# boxer_stm32.net
KiCad netlist of a schematic drawn in Altium Designer
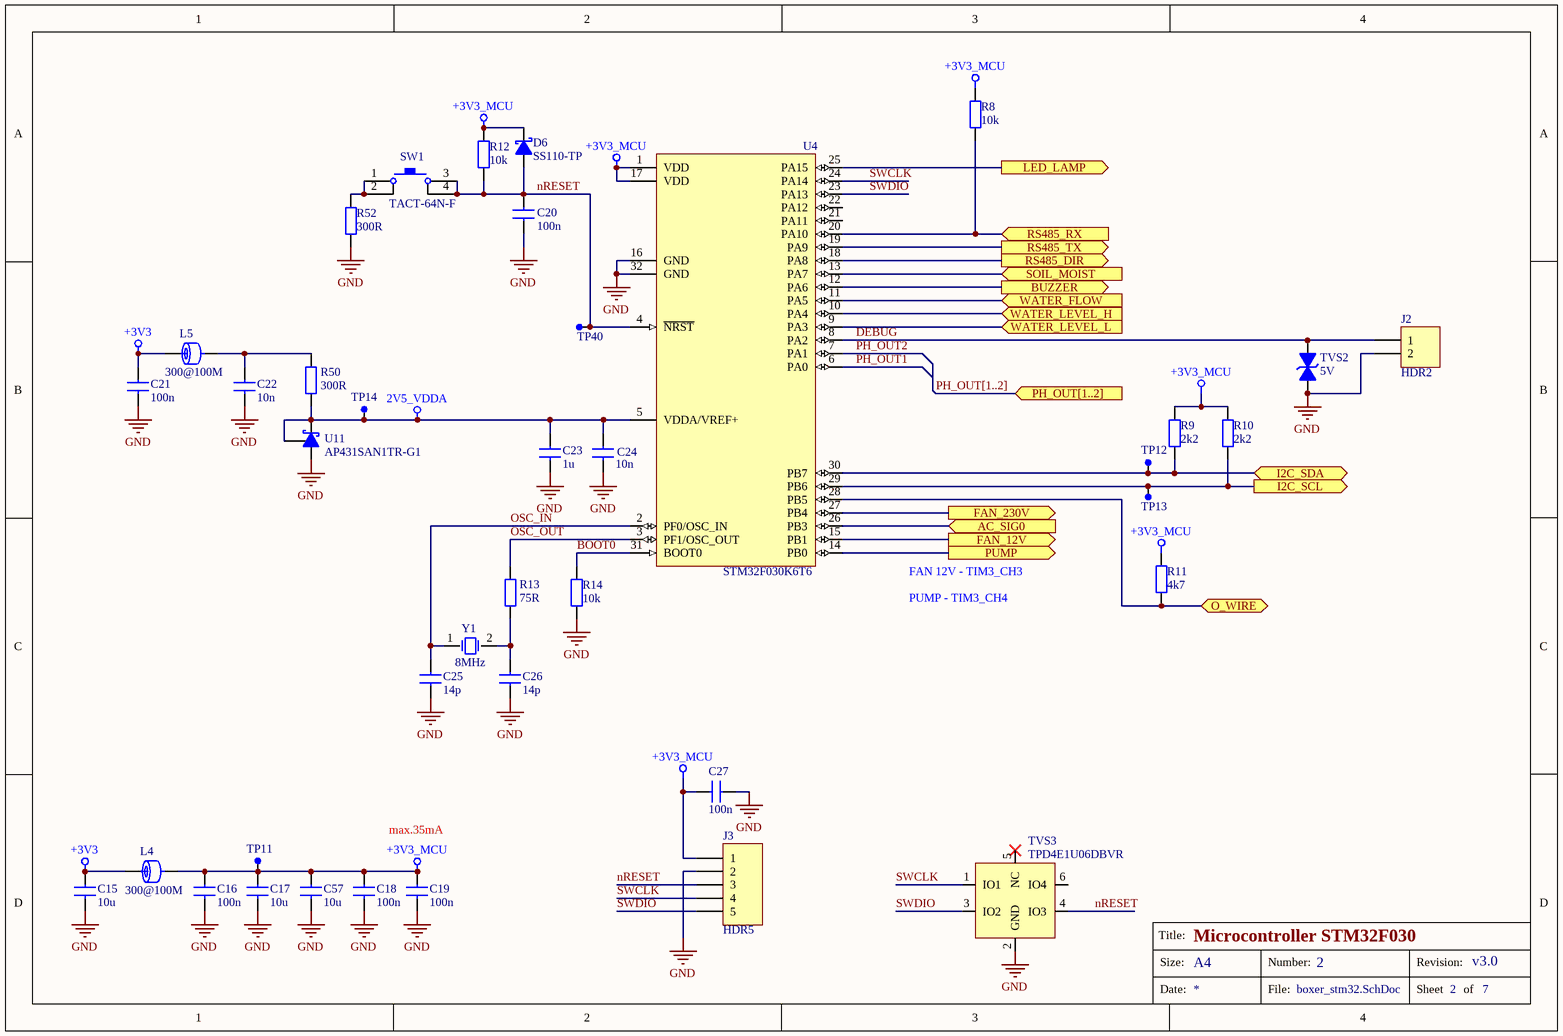
[diagram p0: boxer_stm32.SchDoc]

(export (version "E")
  (design (tool "Eeschema 10.0.6"))
  (components
    (comp (ref "C15")
      (value "10u")
      (footprint "C_1206")
      (description "Capacitor")
      (libsource (lib "boxer_pas") (part "Capacitor"))
    )
    (comp (ref "C16")
      (value "100n")
      (footprint "C_0805")
      (description "Capacitor")
      (libsource (lib "boxer_pas") (part "Capacitor"))
    )
    (comp (ref "C17")
      (value "10u")
      (footprint "C_1206")
      (description "Capacitor")
      (fields (field (name "Comment") "TME: CL31A226MOCLNNC"))
      (libsource (lib "boxer_pas") (part "Capacitor"))
    )
    (comp (ref "C18")
      (value "100n")
      (footprint "C_0805")
      (description "Capacitor")
      (libsource (lib "boxer_pas") (part "Capacitor"))
    )
    (comp (ref "C19")
      (value "100n")
      (footprint "C_0805")
      (description "Capacitor")
      (libsource (lib "boxer_pas") (part "Capacitor"))
    )
    (comp (ref "C20")
      (value "100n")
      (footprint "C_0805")
      (description "Capacitor")
      (libsource (lib "boxer_pas") (part "Capacitor"))
    )
    (comp (ref "C21")
      (value "100n")
      (footprint "C_0805")
      (description "Capacitor")
      (libsource (lib "boxer_pas") (part "Capacitor"))
    )
    (comp (ref "C22")
      (value "10n")
      (footprint "C_0805")
      (description "Capacitor")
      (libsource (lib "boxer_pas") (part "Capacitor"))
    )
    (comp (ref "C23")
      (value "1u")
      (footprint "C_0805")
      (description "Capacitor")
      (fields (field (name "Comment") "C0805C105K4RACAUTO"))
      (libsource (lib "boxer_pas") (part "Capacitor"))
    )
    (comp (ref "C24")
      (value "10n")
      (footprint "C_0805")
      (description "Capacitor")
      (libsource (lib "boxer_pas") (part "Capacitor"))
    )
    (comp (ref "C25")
      (value "14p")
      (footprint "C_0805")
      (description "Capacitor")
      (fields (field (name "Comment") "490-14443-1-ND"))
      (libsource (lib "boxer_pas") (part "Capacitor"))
    )
    (comp (ref "C26")
      (value "14p")
      (footprint "C_0805")
      (description "Capacitor")
      (fields (field (name "Comment") "490-14443-1-ND"))
      (libsource (lib "boxer_pas") (part "Capacitor"))
    )
    (comp (ref "C27")
      (value "100n")
      (footprint "C_0805")
      (description "Capacitor")
      (libsource (lib "boxer_pas") (part "Capacitor"))
    )
    (comp (ref "C57")
      (value "10u")
      (footprint "C_1206")
      (description "Capacitor")
      (fields (field (name "Comment") "TME: CL31A226MOCLNNC"))
      (libsource (lib "boxer_pas") (part "Capacitor"))
    )
    (comp (ref "D6")
      (value "SS110-TP")
      (footprint "D_1206")
      (description "Schottky Diode")
      (libsource (lib "boxer_pas") (part "Diode Schottky"))
    )
    (comp (ref "J2")
      (value "HDR2")
      (footprint "header 2.54mm 2pin")
      (description "Header, 2-Pin")
      (fields (field (name "Comment") "Header 2.54mm"))
      (libsource (lib "boxer_mechanical") (part "Header 2"))
    )
    (comp (ref "J3")
      (value "HDR5")
      (footprint "boxer_mechanical:header 2.54mm 5pin")
      (description "Header, 5-Pin")
      (fields (field (name "Comment") "Header 2.54mm"))
      (libsource (lib "boxer_mechanical") (part "Header 5"))
    )
    (comp (ref "L4")
      (value "300@100M")
      (footprint "L_0805")
      (description "Ferrite Bead")
      (fields (field (name "Comment") "742792031"))
      (libsource (lib "boxer_pas") (part "FB"))
    )
    (comp (ref "L5")
      (value "300@100M")
      (footprint "L_0805")
      (description "Ferrite Bead")
      (fields (field (name "Comment") "742792031"))
      (libsource (lib "boxer_pas") (part "FB"))
    )
    (comp (ref "R8")
      (value "10k")
      (footprint "R_1206")
      (description "Resistor")
      (libsource (lib "boxer_pas") (part "Resistor"))
    )
    (comp (ref "R9")
      (value "2k2")
      (footprint "R_0805")
      (description "Resistor")
      (libsource (lib "boxer_pas") (part "Resistor"))
    )
    (comp (ref "R10")
      (value "2k2")
      (footprint "R_0805")
      (description "Resistor")
      (libsource (lib "boxer_pas") (part "Resistor"))
    )
    (comp (ref "R11")
      (value "4k7")
      (footprint "R_0805")
      (description "Resistor")
      (libsource (lib "") (part "Resistor_1"))
    )
    (comp (ref "R12")
      (value "10k")
      (footprint "R_1206")
      (description "Resistor")
      (libsource (lib "boxer_pas") (part "Resistor"))
    )
    (comp (ref "R13")
      (value "75R")
      (footprint "R_0805")
      (description "Resistor")
      (libsource (lib "boxer_pas") (part "Resistor"))
    )
    (comp (ref "R14")
      (value "10k")
      (footprint "R_1206")
      (description "Resistor")
      (libsource (lib "boxer_pas") (part "Resistor"))
    )
    (comp (ref "R50")
      (value "300R")
      (footprint "R_0805")
      (description "Resistor")
      (libsource (lib "boxer_pas") (part "Resistor"))
    )
    (comp (ref "R52")
      (value "300R")
      (footprint "R_0805")
      (description "Resistor")
      (libsource (lib "") (part "Resistor_1"))
    )
    (comp (ref "SW1")
      (value "TACT-64N-F")
      (footprint "SPST_NO_1301")
      (description "Switch 4 Pins")
      (libsource (lib "boxer_mechanical") (part "Switch-PB 4 Pins"))
    )
    (comp (ref "TP11")
      (value "TEST PAD")
      (footprint "PIN")
      (description "PAD 1.5mm")
      (libsource (lib "boxer_mechanical") (part "TEST_PAD"))
    )
    (comp (ref "TP12")
      (value "TEST PAD")
      (footprint "PIN")
      (libsource (lib "boxer_mechanical") (part "TEST_PAD"))
    )
    (comp (ref "TP13")
      (value "TEST PAD")
      (footprint "PIN")
      (libsource (lib "boxer_mechanical") (part "TEST_PAD"))
    )
    (comp (ref "TP14")
      (value "TEST PAD")
      (footprint "PIN")
      (description "PAD 1.5mm")
      (libsource (lib "boxer_mechanical") (part "TEST_PAD"))
    )
    (comp (ref "TP40")
      (value "TEST PAD")
      (footprint "PIN")
      (description "PAD 1.5mm")
      (libsource (lib "boxer_mechanical") (part "TEST_PAD"))
    )
    (comp (ref "TVS2")
      (value "5V")
      (footprint "D_SMA")
      (description "Transil")
      (fields (field (name "Comment") "SMAJ5.0ALFCT-ND"))
      (libsource (lib "boxer_pas") (part "Transil"))
    )
    (comp (ref "TVS3")
      (value "TPD4E1U06DBVR")
      (footprint "SOT23-6")
      (description "TVS Array")
      (libsource (lib "boxer_pas") (part "Transil Array_2"))
    )
    (comp (ref "U4")
      (value "STM32F030K6T6")
      (footprint "LQFP-32")
      (description "Microcontroler ARM; Flash:32kB; 48MHz; SRAM:4kB; LQFP32")
      (libsource (lib "boxer_ic") (part "STM32F030C8T6"))
    )
    (comp (ref "U11")
      (value "AP431SAN1TR-G1")
      (footprint "SOT-23")
      (libsource (lib "boxer_pas") (part "REF_VOLTAGE"))
    )
    (comp (ref "Y1")
      (value "8MHz")
      (footprint "CFPX_217")
      (description "Crystal Oscillator")
      (fields (field (name "Comment") "7A-8.000MAAE-T"))
      (libsource (lib "boxer_pas") (part "XTAL"))
    )
  )
  (nets
    (net (code "1") (name "+3V3") (class "Default")
      (node (ref "C15") (pin "2") (pinfunction "2_2") (pintype "passive"))
      (node (ref "C21") (pin "2") (pinfunction "2_2") (pintype "passive"))
      (node (ref "L4") (pin "1") (pinfunction "1_1") (pintype "passive"))
      (node (ref "L5") (pin "1") (pinfunction "1_1") (pintype "passive"))
    )
    (net (code "2") (name "+3V3_MCU") (class "Default")
      (node (ref "C16") (pin "2") (pinfunction "2_2") (pintype "passive"))
      (node (ref "C17") (pin "2") (pinfunction "2_2") (pintype "passive"))
      (node (ref "C18") (pin "2") (pinfunction "2_2") (pintype "passive"))
      (node (ref "C19") (pin "2") (pinfunction "2_2") (pintype "passive"))
      (node (ref "C27") (pin "1") (pinfunction "1_1") (pintype "passive"))
      (node (ref "C57") (pin "1") (pinfunction "1_1") (pintype "passive"))
      (node (ref "D6") (pin "2") (pinfunction "K_2") (pintype "passive"))
      (node (ref "J3") (pin "1") (pinfunction "1_1") (pintype "passive"))
      (node (ref "L4") (pin "2") (pinfunction "2_2") (pintype "passive"))
      (node (ref "R10") (pin "2") (pinfunction "2_2") (pintype "passive"))
      (node (ref "R11") (pin "1") (pinfunction "1_1") (pintype "passive"))
      (node (ref "R12") (pin "2") (pinfunction "2_2") (pintype "passive"))
      (node (ref "R8") (pin "2") (pinfunction "2_2") (pintype "passive"))
      (node (ref "R9") (pin "2") (pinfunction "2_2") (pintype "passive"))
      (node (ref "TP11") (pin "1") (pinfunction "1_1") (pintype "passive"))
      (node (ref "U4") (pin "1") (pinfunction "VDD_1") (pintype "power_in"))
      (node (ref "U4") (pin "17") (pinfunction "VDD_17") (pintype "power_in"))
    )
    (net (code "3") (name "/AC_SIG0") (class "Default")
      (node (ref "U4") (pin "26") (pinfunction "PB3_26") (pintype "bidirectional"))
    )
    (net (code "4") (name "/BOOT0") (class "Default")
      (node (ref "R14") (pin "2") (pinfunction "2_2") (pintype "passive"))
      (node (ref "U4") (pin "31") (pinfunction "BOOT0_31") (pintype "input"))
    )
    (net (code "5") (name "/BUZZER") (class "Default")
      (node (ref "U4") (pin "12") (pinfunction "PA6_12") (pintype "bidirectional"))
    )
    (net (code "6") (name "/DEBUG") (class "Default")
      (node (ref "J2") (pin "1") (pinfunction "1_1") (pintype "passive"))
      (node (ref "TVS2") (pin "2") (pinfunction "K_2") (pintype "passive"))
      (node (ref "U4") (pin "8") (pinfunction "PA2_8") (pintype "bidirectional"))
    )
    (net (code "7") (name "/FAN_12V") (class "Default")
      (node (ref "U4") (pin "15") (pinfunction "PB1_15") (pintype "bidirectional"))
    )
    (net (code "8") (name "/FAN_230V") (class "Default")
      (node (ref "U4") (pin "27") (pinfunction "PB4_27") (pintype "bidirectional"))
    )
    (net (code "9") (name "/I2C_SCL") (class "Default")
      (node (ref "R10") (pin "1") (pinfunction "1_1") (pintype "passive"))
      (node (ref "TP13") (pin "1") (pinfunction "1_1") (pintype "passive"))
      (node (ref "U4") (pin "29") (pinfunction "PB6_29") (pintype "bidirectional"))
    )
    (net (code "10") (name "/I2C_SDA") (class "Default")
      (node (ref "R9") (pin "1") (pinfunction "1_1") (pintype "passive"))
      (node (ref "TP12") (pin "1") (pinfunction "1_1") (pintype "passive"))
      (node (ref "U4") (pin "30") (pinfunction "PB7_30") (pintype "bidirectional"))
    )
    (net (code "11") (name "/LED_LAMP") (class "Default")
      (node (ref "U4") (pin "25") (pinfunction "PA15_25") (pintype "bidirectional"))
    )
    (net (code "12") (name "/OSC_IN") (class "Default")
      (node (ref "C25") (pin "2") (pinfunction "2_2") (pintype "passive"))
      (node (ref "U4") (pin "2") (pinfunction "PF0/OSC_IN_2") (pintype "bidirectional"))
      (node (ref "Y1") (pin "1") (pinfunction "OSC1_1") (pintype "passive"))
    )
    (net (code "13") (name "/OSC_OUT") (class "Default")
      (node (ref "R13") (pin "2") (pinfunction "2_2") (pintype "passive"))
      (node (ref "U4") (pin "3") (pinfunction "PF1/OSC_OUT_3") (pintype "bidirectional"))
    )
    (net (code "14") (name "/O_WIRE") (class "Default")
      (node (ref "R11") (pin "2") (pinfunction "2_2") (pintype "passive"))
      (node (ref "U4") (pin "28") (pinfunction "PB5_28") (pintype "bidirectional"))
    )
    (net (code "15") (name "/PH_OUT1") (class "Default")
      (node (ref "U4") (pin "6") (pinfunction "PA0_6") (pintype "bidirectional"))
    )
    (net (code "16") (name "/PH_OUT2") (class "Default")
      (node (ref "U4") (pin "7") (pinfunction "PA1_7") (pintype "bidirectional"))
    )
    (net (code "18") (name "/PUMP") (class "Default")
      (node (ref "U4") (pin "14") (pinfunction "PB0_14") (pintype "bidirectional"))
    )
    (net (code "19") (name "/RS485_DIR") (class "Default")
      (node (ref "U4") (pin "18") (pinfunction "PA8_18") (pintype "bidirectional"))
    )
    (net (code "20") (name "/RS485_RX") (class "Default")
      (node (ref "R8") (pin "1") (pinfunction "1_1") (pintype "passive"))
      (node (ref "U4") (pin "20") (pinfunction "PA10_20") (pintype "bidirectional"))
    )
    (net (code "21") (name "/RS485_TX") (class "Default")
      (node (ref "U4") (pin "19") (pinfunction "PA9_19") (pintype "bidirectional"))
    )
    (net (code "22") (name "/SOIL_MOIST") (class "Default")
      (node (ref "U4") (pin "13") (pinfunction "PA7_13") (pintype "bidirectional"))
    )
    (net (code "23") (name "/SWCLK") (class "Default")
      (node (ref "J3") (pin "4") (pinfunction "4_4") (pintype "passive"))
      (node (ref "TVS3") (pin "1") (pinfunction "IO1_1") (pintype "passive"))
      (node (ref "U4") (pin "24") (pinfunction "PA14_24") (pintype "bidirectional"))
    )
    (net (code "24") (name "/SWDIO") (class "Default")
      (node (ref "J3") (pin "5") (pinfunction "5_5") (pintype "passive"))
      (node (ref "TVS3") (pin "3") (pinfunction "IO2_3") (pintype "passive"))
      (node (ref "U4") (pin "23") (pinfunction "PA13_23") (pintype "bidirectional"))
    )
    (net (code "25") (name "/WATER_FLOW") (class "Default")
      (node (ref "U4") (pin "11") (pinfunction "PA5_11") (pintype "bidirectional"))
    )
    (net (code "26") (name "/WATER_LEVEL_H") (class "Default")
      (node (ref "U4") (pin "10") (pinfunction "PA4_10") (pintype "bidirectional"))
    )
    (net (code "27") (name "/WATER_LEVEL_L") (class "Default")
      (node (ref "U4") (pin "9") (pinfunction "PA3_9") (pintype "bidirectional"))
    )
    (net (code "28") (name "/nRESET") (class "Default")
      (node (ref "C20") (pin "2") (pinfunction "2_2") (pintype "passive"))
      (node (ref "D6") (pin "1") (pinfunction "A_1") (pintype "passive"))
      (node (ref "J3") (pin "3") (pinfunction "3_3") (pintype "passive"))
      (node (ref "R12") (pin "1") (pinfunction "1_1") (pintype "passive"))
      (node (ref "SW1") (pin "3") (pinfunction "3_3") (pintype "passive"))
      (node (ref "SW1") (pin "4") (pinfunction "4_4") (pintype "passive"))
      (node (ref "TP40") (pin "1") (pinfunction "1_1") (pintype "passive"))
      (node (ref "TVS3") (pin "4") (pinfunction "IO3_4") (pintype "passive"))
      (node (ref "U4") (pin "4") (pinfunction "~{NRST}_4") (pintype "input"))
    )
    (net (code "29") (name "2V5_VDDA") (class "Default")
      (node (ref "C23") (pin "2") (pinfunction "2_2") (pintype "passive"))
      (node (ref "C24") (pin "2") (pinfunction "2_2") (pintype "passive"))
      (node (ref "R50") (pin "1") (pinfunction "1_1") (pintype "passive"))
      (node (ref "TP14") (pin "1") (pinfunction "1_1") (pintype "passive"))
      (node (ref "U11") (pin "1") (pinfunction "REF_1") (pintype "passive"))
      (node (ref "U11") (pin "2") (pinfunction "K_2") (pintype "passive"))
      (node (ref "U4") (pin "5") (pinfunction "VDDA/VREF+_5") (pintype "power_in"))
    )
    (net (code "30") (name "GND") (class "Default")
      (node (ref "C15") (pin "1") (pinfunction "1_1") (pintype "passive"))
      (node (ref "C16") (pin "1") (pinfunction "1_1") (pintype "passive"))
      (node (ref "C17") (pin "1") (pinfunction "1_1") (pintype "passive"))
      (node (ref "C18") (pin "1") (pinfunction "1_1") (pintype "passive"))
      (node (ref "C19") (pin "1") (pinfunction "1_1") (pintype "passive"))
      (node (ref "C20") (pin "1") (pinfunction "1_1") (pintype "passive"))
      (node (ref "C21") (pin "1") (pinfunction "1_1") (pintype "passive"))
      (node (ref "C22") (pin "1") (pinfunction "1_1") (pintype "passive"))
      (node (ref "C23") (pin "1") (pinfunction "1_1") (pintype "passive"))
      (node (ref "C24") (pin "1") (pinfunction "1_1") (pintype "passive"))
      (node (ref "C25") (pin "1") (pinfunction "1_1") (pintype "passive"))
      (node (ref "C26") (pin "1") (pinfunction "1_1") (pintype "passive"))
      (node (ref "C27") (pin "2") (pinfunction "2_2") (pintype "passive"))
      (node (ref "C57") (pin "2") (pinfunction "2_2") (pintype "passive"))
      (node (ref "J2") (pin "2") (pinfunction "2_2") (pintype "passive"))
      (node (ref "J3") (pin "2") (pinfunction "2_2") (pintype "passive"))
      (node (ref "R14") (pin "1") (pinfunction "1_1") (pintype "passive"))
      (node (ref "R52") (pin "2") (pinfunction "2_2") (pintype "passive"))
      (node (ref "TVS2") (pin "1") (pinfunction "A_1") (pintype "passive"))
      (node (ref "TVS3") (pin "2") (pinfunction "GND_2") (pintype "power_in"))
      (node (ref "U11") (pin "3") (pinfunction "A_3") (pintype "passive"))
      (node (ref "U4") (pin "16") (pinfunction "GND_16") (pintype "power_in"))
      (node (ref "U4") (pin "32") (pinfunction "GND_32") (pintype "power_in"))
    )
    (net (code "31") (name "Net-(C22-Pad2)") (class "Default")
      (node (ref "C22") (pin "2") (pinfunction "2_2") (pintype "passive"))
      (node (ref "L5") (pin "2") (pinfunction "2_2") (pintype "passive"))
      (node (ref "R50") (pin "2") (pinfunction "2_2") (pintype "passive"))
    )
    (net (code "32") (name "Net-(R52-Pad1)") (class "Default")
      (node (ref "R52") (pin "1") (pinfunction "1_1") (pintype "passive"))
      (node (ref "SW1") (pin "1") (pinfunction "1_1") (pintype "passive"))
      (node (ref "SW1") (pin "2") (pinfunction "2_2") (pintype "passive"))
    )
    (net (code "33") (name "Net-(Y1-OSC2)") (class "Default")
      (node (ref "C26") (pin "2") (pinfunction "2_2") (pintype "passive"))
      (node (ref "R13") (pin "1") (pinfunction "1_1") (pintype "passive"))
      (node (ref "Y1") (pin "2") (pinfunction "OSC2_2") (pintype "passive"))
    )
    (net (code "34") (name "unconnected-(TVS3-IO4-Pad6)") (class "Default")
      (node (ref "TVS3") (pin "6") (pinfunction "IO4_6") (pintype "passive"))
    )
    (net (code "35") (name "unconnected-(TVS3-NC-Pad5)") (class "Default")
      (node (ref "TVS3") (pin "5") (pinfunction "NC_5") (pintype "passive+no_connect"))
    )
    (net (code "36") (name "unconnected-(U4-PA11-Pad21)") (class "Default")
      (node (ref "U4") (pin "21") (pinfunction "PA11_21") (pintype "bidirectional"))
    )
    (net (code "37") (name "unconnected-(U4-PA12-Pad22)") (class "Default")
      (node (ref "U4") (pin "22") (pinfunction "PA12_22") (pintype "bidirectional"))
    )
  )
)
